# main.net
KiCad netlist of a schematic drawn in Altium Designer
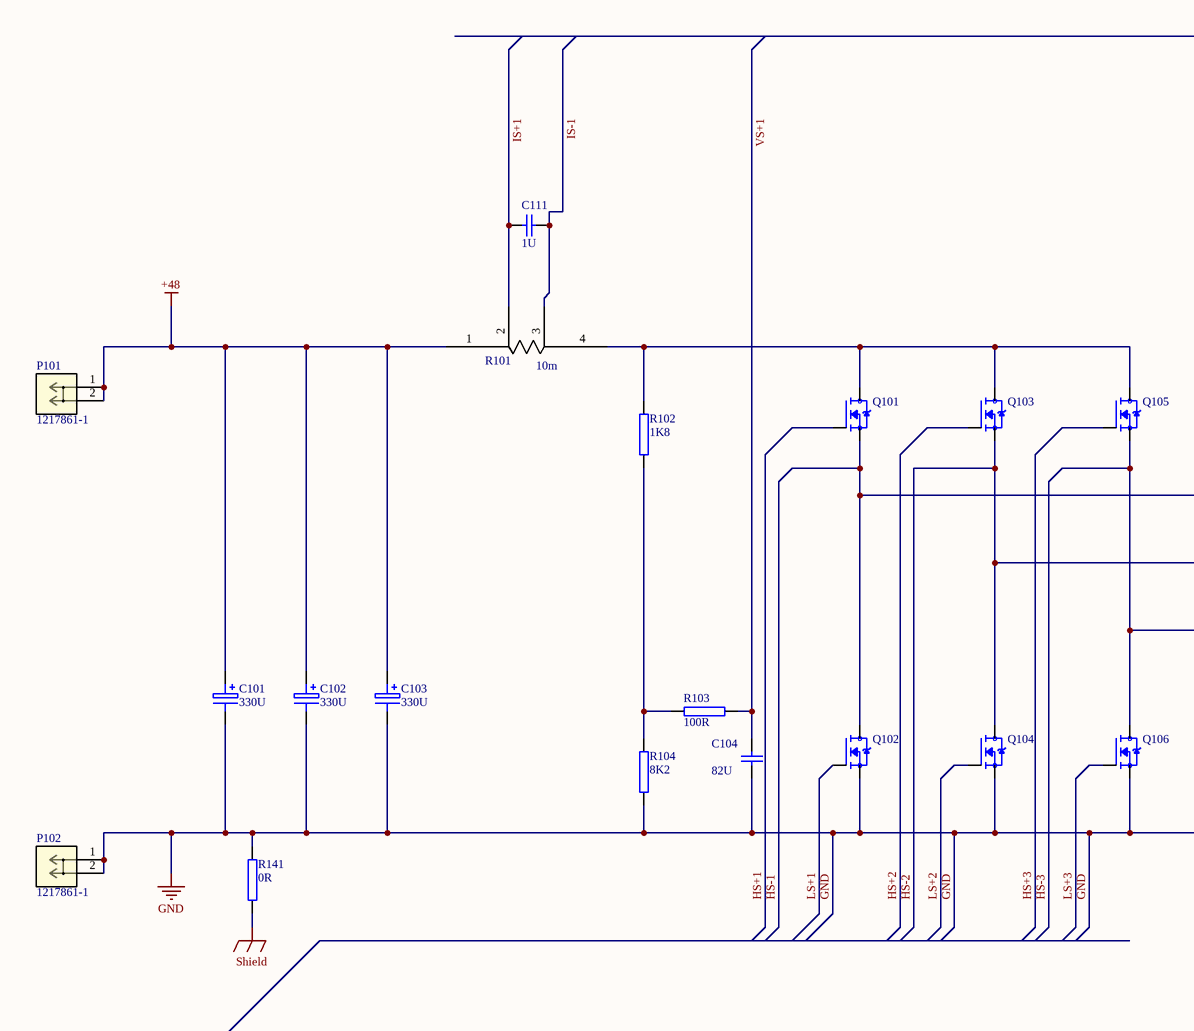
[diagram p0: main.SchDoc, top left]
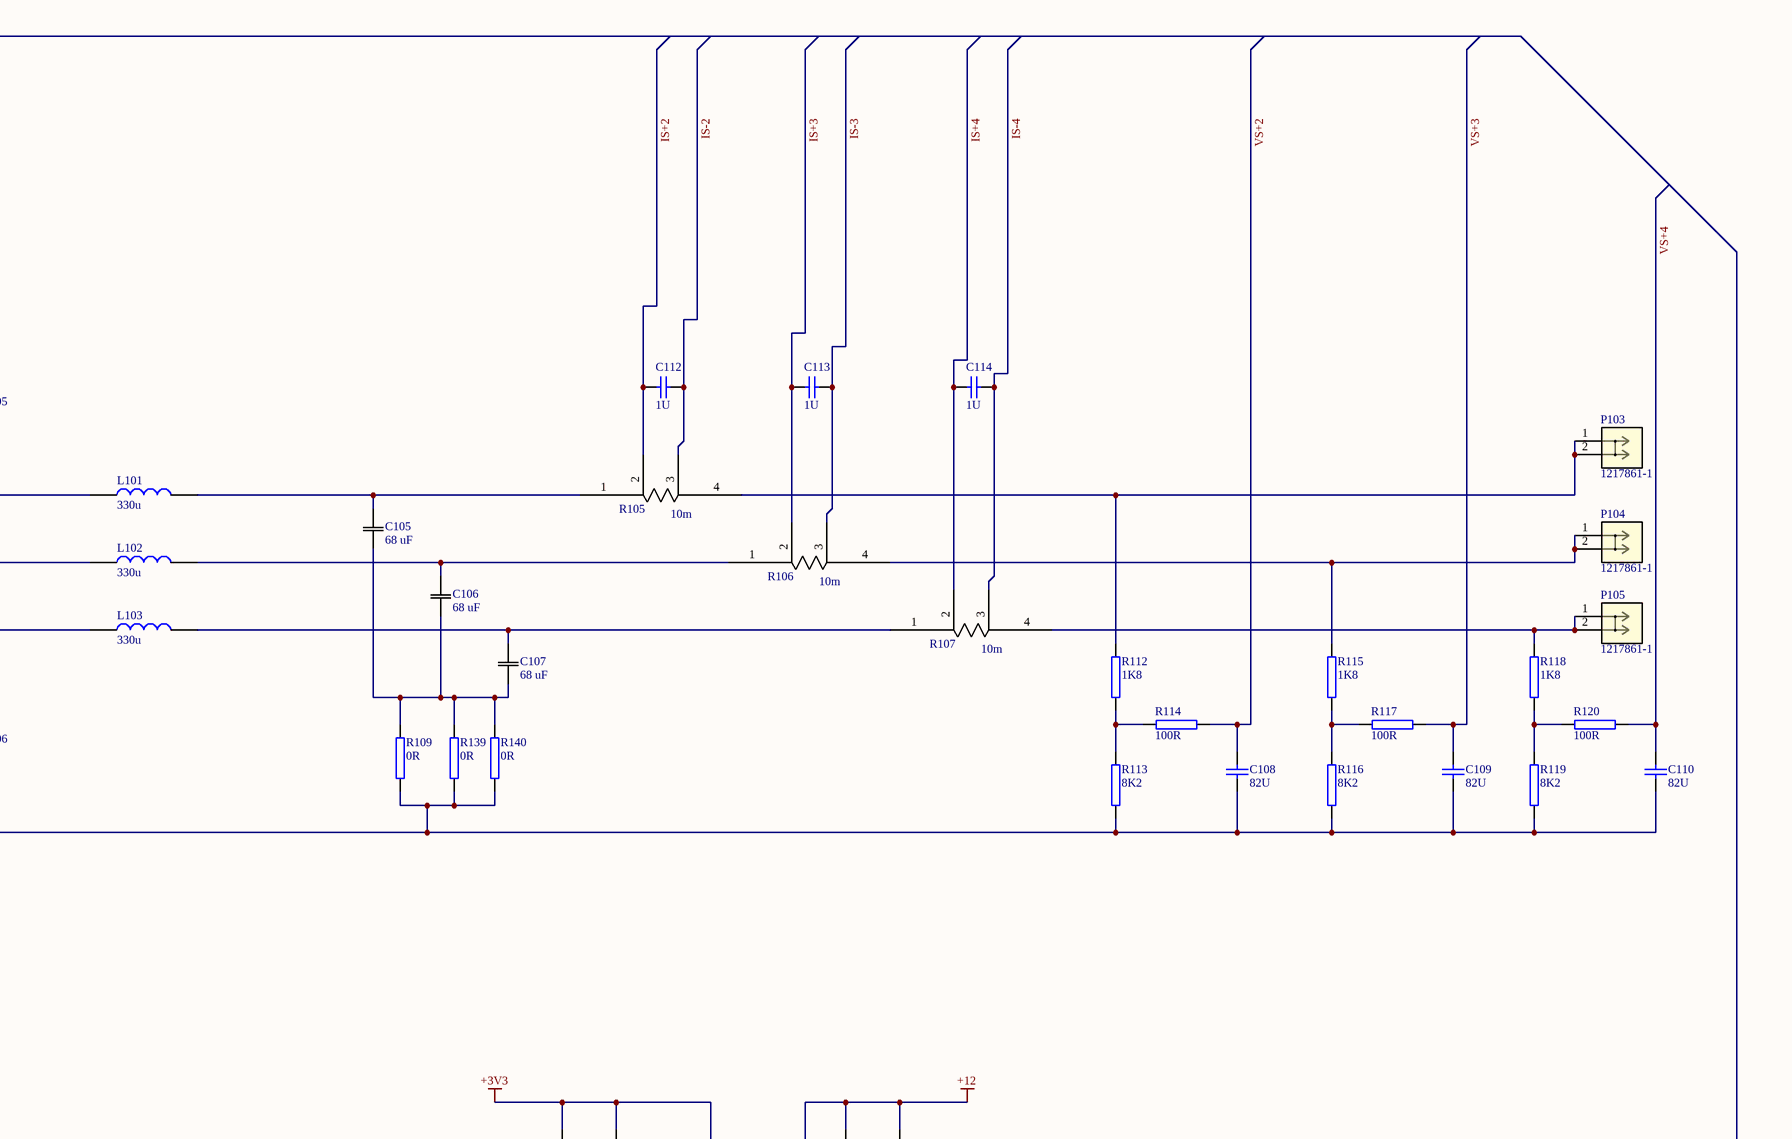
[diagram p1: main.SchDoc, top right]
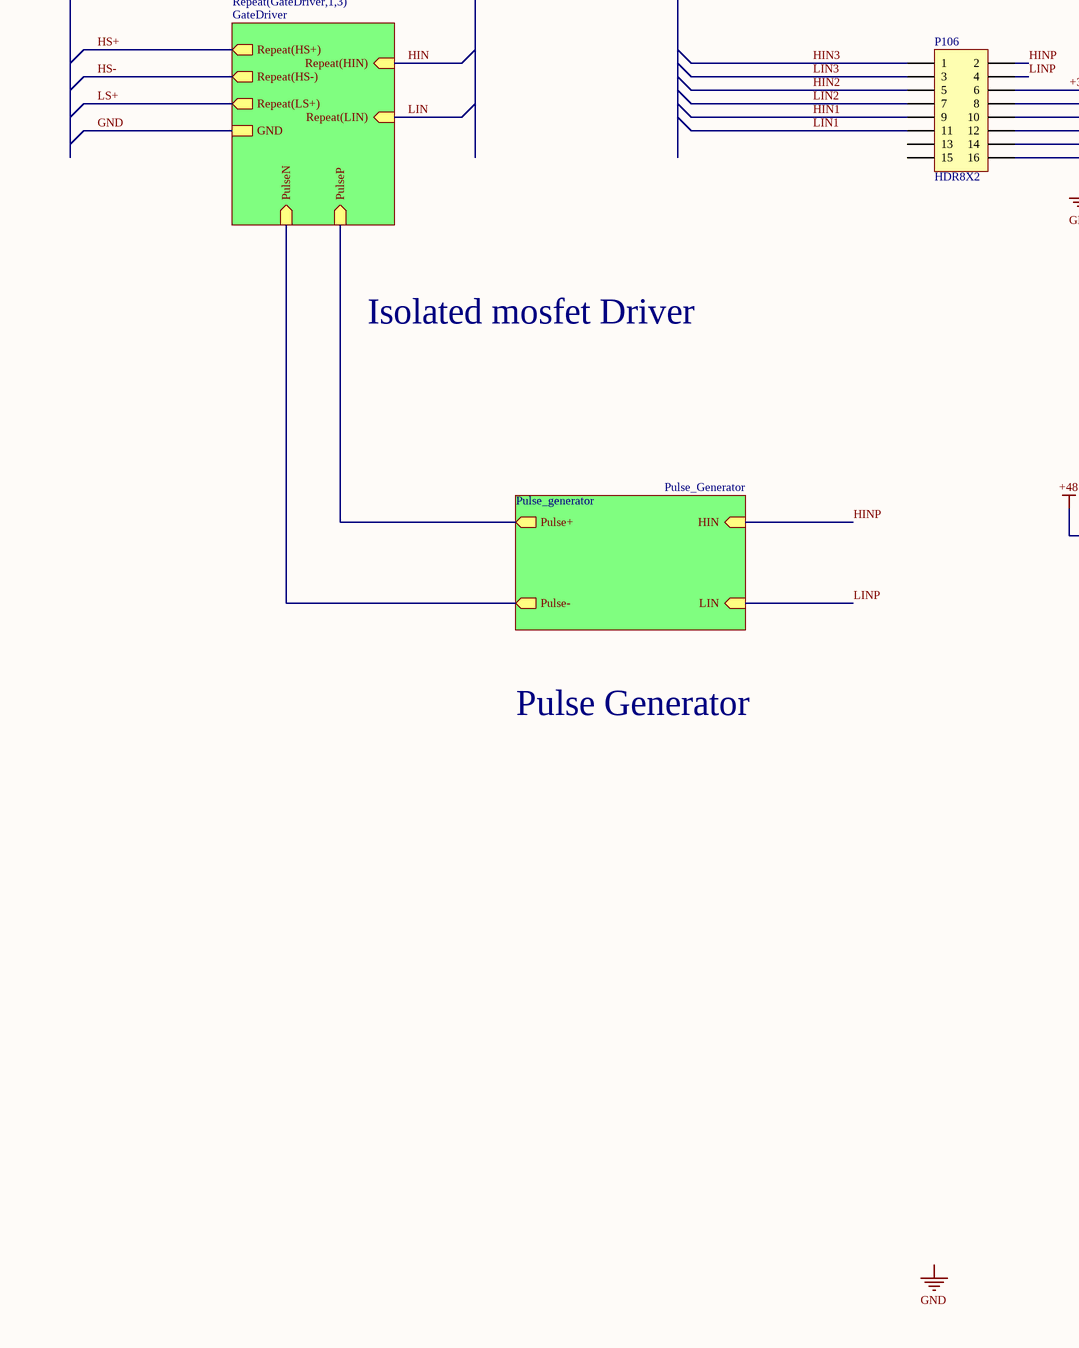
[diagram p2: main.SchDoc, bottom left]
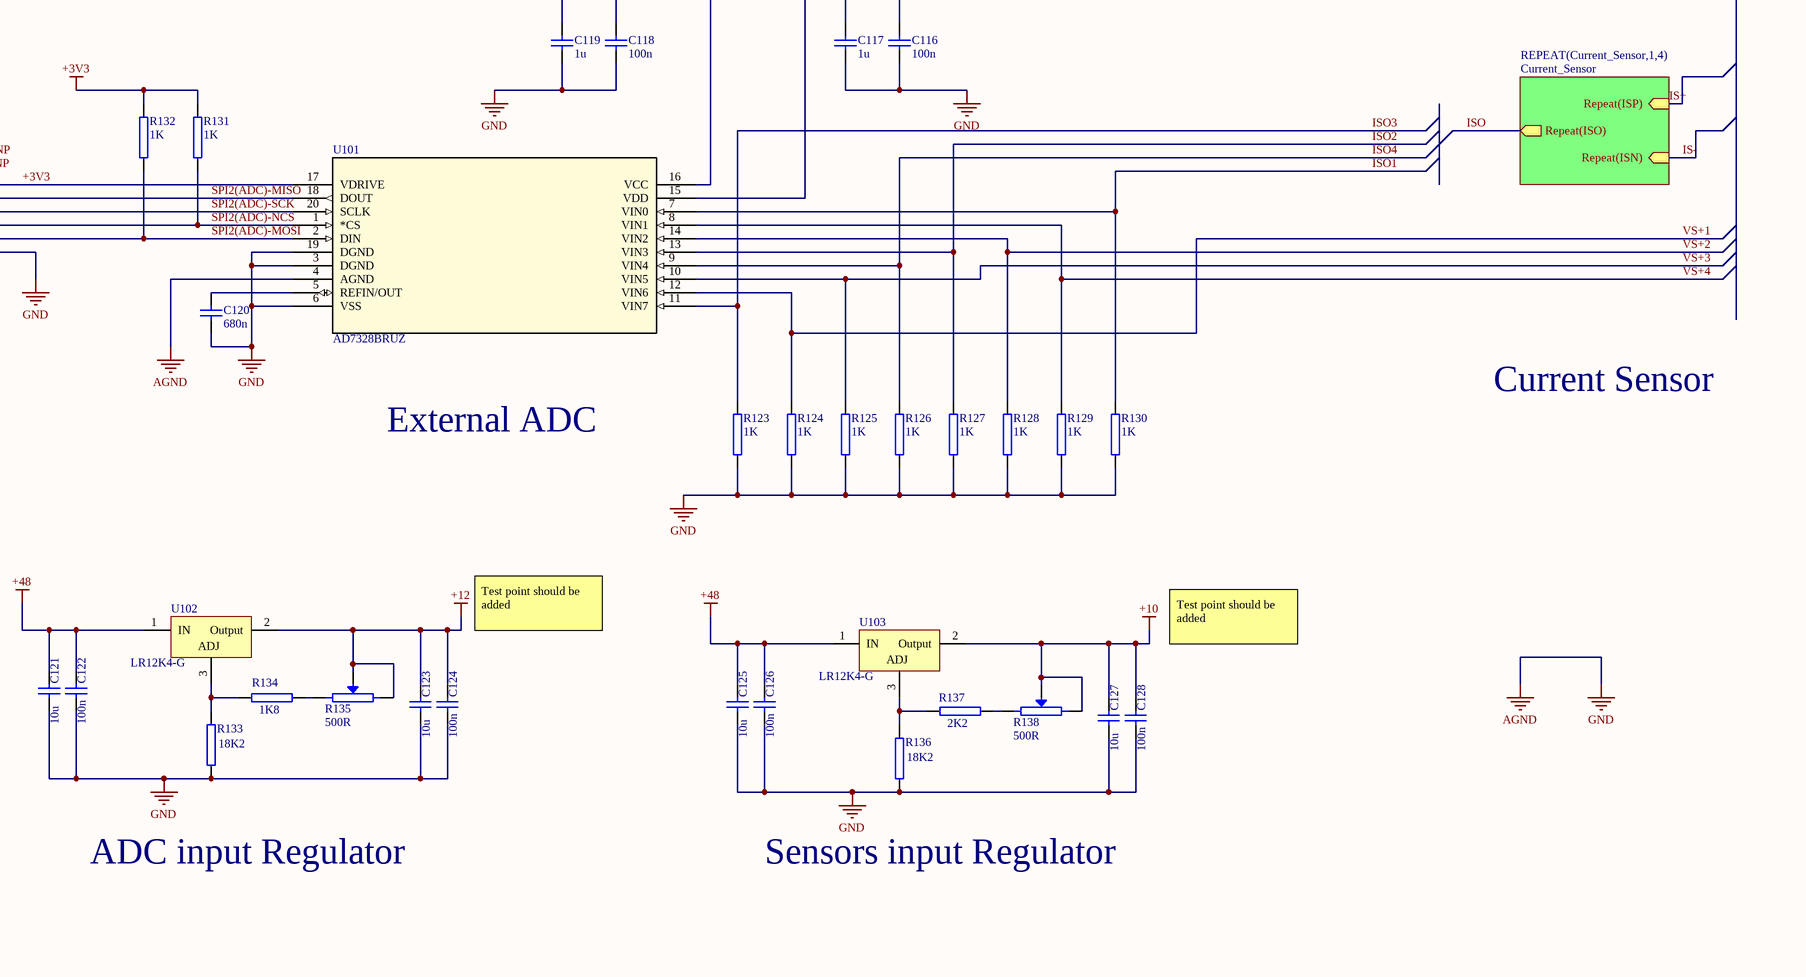
[diagram p3: main.SchDoc, bottom right]

(export (version "E")
  (design (tool "Eeschema 10.0.6"))
  (components
    (comp (ref "C101")
      (value "330U")
      (footprint "CAPP300-600_AUT")
      (description "Polarized Aluminum Capacitor, Through Hole, Pitch 300mil, Body 600mil (Dia)")
      (libsource (lib "Resistors and Capacitors") (part "CAPP300-600"))
    )
    (comp (ref "C102")
      (value "330U")
      (footprint "CAPP300-600_AUT")
      (description "Polarized Aluminum Capacitor, Through Hole, Pitch 300mil, Body 600mil (Dia)")
      (libsource (lib "Resistors and Capacitors") (part "CAPP300-600"))
    )
    (comp (ref "C103")
      (value "330U")
      (footprint "CAPP300-600_AUT")
      (description "Polarized Aluminum Capacitor, Through Hole, Pitch 300mil, Body 600mil (Dia)")
      (libsource (lib "Resistors and Capacitors") (part "CAPP300-600"))
    )
    (comp (ref "C104")
      (value "82U")
      (footprint "CAP_1206")
      (description "Non Polarized Capacitor, SMD, 1206")
      (libsource (lib "Resistors and Capacitors") (part "CAPN 1206"))
    )
    (comp (ref "C105")
      (value "68 uF")
      (footprint "B32526R3686K000")
      (libsource (lib "ENEL709_Schematic_Library") (part "B32526R3686K000"))
    )
    (comp (ref "C106")
      (value "68 uF")
      (footprint "B32526R3686K000")
      (libsource (lib "ENEL709_Schematic_Library") (part "B32526R3686K000"))
    )
    (comp (ref "C107")
      (value "68 uF")
      (footprint "B32526R3686K000")
      (libsource (lib "ENEL709_Schematic_Library") (part "B32526R3686K000"))
    )
    (comp (ref "C108")
      (value "82U")
      (footprint "CAP_1206")
      (description "Non Polarized Capacitor, SMD, 1206")
      (libsource (lib "Resistors and Capacitors") (part "CAPN 1206"))
    )
    (comp (ref "C109")
      (value "82U")
      (footprint "CAP_1206")
      (description "Non Polarized Capacitor, SMD, 1206")
      (libsource (lib "Resistors and Capacitors") (part "CAPN 1206"))
    )
    (comp (ref "C110")
      (value "82U")
      (footprint "CAP_1206")
      (description "Non Polarized Capacitor, SMD, 1206")
      (libsource (lib "Resistors and Capacitors") (part "CAPN 1206"))
    )
    (comp (ref "C111")
      (value "1U")
      (footprint "CAP_1206")
      (description "Non Polarized Capacitor, SMD, 1206")
      (libsource (lib "Resistors and Capacitors") (part "CAPN 1206"))
    )
    (comp (ref "C112")
      (value "1U")
      (footprint "CAP_1206")
      (description "Non Polarized Capacitor, SMD, 1206")
      (libsource (lib "Resistors and Capacitors") (part "CAPN 1206"))
    )
    (comp (ref "C113")
      (value "1U")
      (footprint "CAP_1206")
      (description "Non Polarized Capacitor, SMD, 1206")
      (libsource (lib "Resistors and Capacitors") (part "CAPN 1206"))
    )
    (comp (ref "C114")
      (value "1U")
      (footprint "CAP_1206")
      (description "Non Polarized Capacitor, SMD, 1206")
      (libsource (lib "Resistors and Capacitors") (part "CAPN 1206"))
    )
    (comp (ref "C116")
      (value "100n")
      (footprint "CAP_1206")
      (description "Non Polarized Capacitor, SMD, 1206")
      (libsource (lib "Resistors and Capacitors") (part "CAPN 1206"))
    )
    (comp (ref "C117")
      (value "1u")
      (footprint "CAP_1206")
      (description "Non Polarized Capacitor, SMD, 1206")
      (libsource (lib "Resistors and Capacitors") (part "CAPN 1206"))
    )
    (comp (ref "C118")
      (value "100n")
      (footprint "CAP_1206")
      (description "Non Polarized Capacitor, SMD, 1206")
      (libsource (lib "Resistors and Capacitors") (part "CAPN 1206"))
    )
    (comp (ref "C119")
      (value "1u")
      (footprint "CAP_1206")
      (description "Non Polarized Capacitor, SMD, 1206")
      (libsource (lib "Resistors and Capacitors") (part "CAPN 1206"))
    )
    (comp (ref "C120")
      (value "680n")
      (footprint "CAP_1206")
      (description "Non Polarized Capacitor, SMD, 1206")
      (libsource (lib "Resistors and Capacitors") (part "CAPN 1206"))
    )
    (comp (ref "C121")
      (value "10u")
      (footprint "CAP_1206")
      (description "Non Polarized Capacitor, SMD, 1206")
      (libsource (lib "Resistors and Capacitors") (part "CAPN 1206"))
    )
    (comp (ref "C122")
      (value "100n")
      (footprint "CAP_1206")
      (description "Non Polarized Capacitor, SMD, 1206")
      (libsource (lib "Resistors and Capacitors") (part "CAPN 1206"))
    )
    (comp (ref "C123")
      (value "10u")
      (footprint "CAP_1206")
      (description "Non Polarized Capacitor, SMD, 1206")
      (libsource (lib "Resistors and Capacitors") (part "CAPN 1206"))
    )
    (comp (ref "C124")
      (value "100n")
      (footprint "CAP_1206")
      (description "Non Polarized Capacitor, SMD, 1206")
      (libsource (lib "Resistors and Capacitors") (part "CAPN 1206"))
    )
    (comp (ref "C125")
      (value "10u")
      (footprint "CAP_1206")
      (description "Non Polarized Capacitor, SMD, 1206")
      (libsource (lib "Resistors and Capacitors") (part "CAPN 1206"))
    )
    (comp (ref "C126")
      (value "100n")
      (footprint "CAP_1206")
      (description "Non Polarized Capacitor, SMD, 1206")
      (libsource (lib "Resistors and Capacitors") (part "CAPN 1206"))
    )
    (comp (ref "C127")
      (value "10u")
      (footprint "CAP_1206")
      (description "Non Polarized Capacitor, SMD, 1206")
      (libsource (lib "Resistors and Capacitors") (part "CAPN 1206"))
    )
    (comp (ref "C128")
      (value "100n")
      (footprint "CAP_1206")
      (description "Non Polarized Capacitor, SMD, 1206")
      (libsource (lib "Resistors and Capacitors") (part "CAPN 1206"))
    )
    (comp (ref "L101")
      (value "330u")
      (footprint "1140-331K-RC")
      (libsource (lib "ENEL709_Schematic_Library") (part "1140-331K-RC"))
    )
    (comp (ref "L102")
      (value "330u")
      (footprint "1140-331K-RC")
      (libsource (lib "ENEL709_Schematic_Library") (part "1140-331K-RC"))
    )
    (comp (ref "L103")
      (value "330u")
      (footprint "1140-331K-RC")
      (libsource (lib "ENEL709_Schematic_Library") (part "1140-331K-RC"))
    )
    (comp (ref "P101")
      (value "1217861-1")
      (footprint "CONN_1217861-1_TEC")
      (libsource (lib "") (part "1217861-1_1"))
    )
    (comp (ref "P102")
      (value "1217861-1")
      (footprint "CONN_1217861-1_TEC")
      (libsource (lib "") (part "1217861-1_1"))
    )
    (comp (ref "P103")
      (value "1217861-1")
      (footprint "CONN_1217861-1_TEC")
      (libsource (lib "Schlib") (part "1217861-1"))
    )
    (comp (ref "P104")
      (value "1217861-1")
      (footprint "CONN_1217861-1_TEC")
      (libsource (lib "Schlib") (part "1217861-1"))
    )
    (comp (ref "P105")
      (value "1217861-1")
      (footprint "CONN_1217861-1_TEC")
      (libsource (lib "Schlib") (part "1217861-1"))
    )
    (comp (ref "P106")
      (value "HDR8X2")
      (footprint "HDR2X8_AUT")
      (description "Header, 8-Pin, Dual row, 2.54mm Pitch, Straight")
      (libsource (lib "Connectors") (part "HDR8X2"))
    )
    (comp (ref "Q101")
      (value "MCTL80N20Y-TP")
      (footprint "TOLL-8L")
      (description "N-Channel 200 V 80A (Tc) 250W (Tj) Surface Mount TOLL-8L")
      (libsource (lib "Projects_2025") (part "MCTL80N20Y-TP"))
    )
    (comp (ref "Q102")
      (value "MCTL80N20Y-TP")
      (footprint "TOLL-8L")
      (description "N-Channel 200 V 80A (Tc) 250W (Tj) Surface Mount TOLL-8L")
      (libsource (lib "Projects_2025") (part "MCTL80N20Y-TP"))
    )
    (comp (ref "Q103")
      (value "MCTL80N20Y-TP")
      (footprint "TOLL-8L")
      (description "N-Channel 200 V 80A (Tc) 250W (Tj) Surface Mount TOLL-8L")
      (libsource (lib "Projects_2025") (part "MCTL80N20Y-TP"))
    )
    (comp (ref "Q104")
      (value "MCTL80N20Y-TP")
      (footprint "TOLL-8L")
      (description "N-Channel 200 V 80A (Tc) 250W (Tj) Surface Mount TOLL-8L")
      (libsource (lib "Projects_2025") (part "MCTL80N20Y-TP"))
    )
    (comp (ref "Q105")
      (value "MCTL80N20Y-TP")
      (footprint "TOLL-8L")
      (description "N-Channel 200 V 80A (Tc) 250W (Tj) Surface Mount TOLL-8L")
      (libsource (lib "Projects_2025") (part "MCTL80N20Y-TP"))
    )
    (comp (ref "Q106")
      (value "MCTL80N20Y-TP")
      (footprint "TOLL-8L")
      (description "N-Channel 200 V 80A (Tc) 250W (Tj) Surface Mount TOLL-8L")
      (libsource (lib "Projects_2025") (part "MCTL80N20Y-TP"))
    )
    (comp (ref "R101")
      (value "10m")
      (footprint "WSL3673R_002-01")
      (description "Current Shunt \r\nKelvin 4W 0.002- 0.01")
      (libsource (lib "Projects_2025") (part "WSL3673R-01"))
    )
    (comp (ref "R102")
      (value "1K8")
      (footprint "RES_1206")
      (description "Resistor, SMD, 1206")
      (libsource (lib "Resistors and Capacitors") (part "Resistor 1206"))
    )
    (comp (ref "R103")
      (value "100R")
      (footprint "RES_1206")
      (description "Resistor, SMD, 1206")
      (libsource (lib "Resistors and Capacitors") (part "Resistor 1206"))
    )
    (comp (ref "R104")
      (value "8K2")
      (footprint "RES_1206")
      (description "Resistor, SMD, 1206")
      (libsource (lib "Resistors and Capacitors") (part "Resistor 1206"))
    )
    (comp (ref "R105")
      (value "10m")
      (footprint "WSL3673R_002-01")
      (description "Current Shunt \r\nKelvin 4W 0.002- 0.01")
      (libsource (lib "Projects_2025") (part "WSL3673R-01"))
    )
    (comp (ref "R106")
      (value "10m")
      (footprint "WSL3673R_002-01")
      (description "Current Shunt \r\nKelvin 4W 0.002- 0.01")
      (libsource (lib "Projects_2025") (part "WSL3673R-01"))
    )
    (comp (ref "R107")
      (value "10m")
      (footprint "WSL3673R_002-01")
      (description "Current Shunt \r\nKelvin 4W 0.002- 0.01")
      (libsource (lib "Projects_2025") (part "WSL3673R-01"))
    )
    (comp (ref "R109")
      (value "0R")
      (footprint "RES_1206")
      (description "Resistor, SMD, 1206")
      (libsource (lib "Resistors and Capacitors") (part "Resistor 1206"))
    )
    (comp (ref "R112")
      (value "1K8")
      (footprint "RES_1206")
      (description "Resistor, SMD, 1206")
      (libsource (lib "Resistors and Capacitors") (part "Resistor 1206"))
    )
    (comp (ref "R113")
      (value "8K2")
      (footprint "RES_1206")
      (description "Resistor, SMD, 1206")
      (libsource (lib "Resistors and Capacitors") (part "Resistor 1206"))
    )
    (comp (ref "R114")
      (value "100R")
      (footprint "RES_1206")
      (description "Resistor, SMD, 1206")
      (libsource (lib "Resistors and Capacitors") (part "Resistor 1206"))
    )
    (comp (ref "R115")
      (value "1K8")
      (footprint "RES_1206")
      (description "Resistor, SMD, 1206")
      (libsource (lib "Resistors and Capacitors") (part "Resistor 1206"))
    )
    (comp (ref "R116")
      (value "8K2")
      (footprint "RES_1206")
      (description "Resistor, SMD, 1206")
      (libsource (lib "Resistors and Capacitors") (part "Resistor 1206"))
    )
    (comp (ref "R117")
      (value "100R")
      (footprint "RES_1206")
      (description "Resistor, SMD, 1206")
      (libsource (lib "Resistors and Capacitors") (part "Resistor 1206"))
    )
    (comp (ref "R118")
      (value "1K8")
      (footprint "RES_1206")
      (description "Resistor, SMD, 1206")
      (libsource (lib "Resistors and Capacitors") (part "Resistor 1206"))
    )
    (comp (ref "R119")
      (value "8K2")
      (footprint "RES_1206")
      (description "Resistor, SMD, 1206")
      (libsource (lib "Resistors and Capacitors") (part "Resistor 1206"))
    )
    (comp (ref "R120")
      (value "100R")
      (footprint "RES_1206")
      (description "Resistor, SMD, 1206")
      (libsource (lib "Resistors and Capacitors") (part "Resistor 1206"))
    )
    (comp (ref "R123")
      (value "1K")
      (footprint "RES_1206")
      (description "Resistor, SMD, 1206")
      (libsource (lib "Resistors and Capacitors") (part "Resistor 1206"))
    )
    (comp (ref "R124")
      (value "1K")
      (footprint "RES_1206")
      (description "Resistor, SMD, 1206")
      (libsource (lib "Resistors and Capacitors") (part "Resistor 1206"))
    )
    (comp (ref "R125")
      (value "1K")
      (footprint "RES_1206")
      (description "Resistor, SMD, 1206")
      (libsource (lib "Resistors and Capacitors") (part "Resistor 1206"))
    )
    (comp (ref "R126")
      (value "1K")
      (footprint "RES_1206")
      (description "Resistor, SMD, 1206")
      (libsource (lib "Resistors and Capacitors") (part "Resistor 1206"))
    )
    (comp (ref "R127")
      (value "1K")
      (footprint "RES_1206")
      (description "Resistor, SMD, 1206")
      (libsource (lib "Resistors and Capacitors") (part "Resistor 1206"))
    )
    (comp (ref "R128")
      (value "1K")
      (footprint "RES_1206")
      (description "Resistor, SMD, 1206")
      (libsource (lib "Resistors and Capacitors") (part "Resistor 1206"))
    )
    (comp (ref "R129")
      (value "1K")
      (footprint "RES_1206")
      (description "Resistor, SMD, 1206")
      (libsource (lib "Resistors and Capacitors") (part "Resistor 1206"))
    )
    (comp (ref "R130")
      (value "1K")
      (footprint "RES_1206")
      (description "Resistor, SMD, 1206")
      (libsource (lib "Resistors and Capacitors") (part "Resistor 1206"))
    )
    (comp (ref "R131")
      (value "1K")
      (footprint "RES_1206")
      (description "Resistor, SMD, 1206")
      (libsource (lib "Resistors and Capacitors") (part "Resistor 1206"))
    )
    (comp (ref "R132")
      (value "1K")
      (footprint "RES_1206")
      (description "Resistor, SMD, 1206")
      (libsource (lib "Resistors and Capacitors") (part "Resistor 1206"))
    )
    (comp (ref "R133")
      (value "18K2")
      (footprint "RES_1206")
      (description "Resistor, SMD, 1206")
      (libsource (lib "Resistors and Capacitors") (part "Resistor 1206"))
    )
    (comp (ref "R134")
      (value "1K8")
      (footprint "RES_1206")
      (description "Resistor, SMD, 1206")
      (libsource (lib "Resistors and Capacitors") (part "Resistor 1206"))
    )
    (comp (ref "R135")
      (value "500R")
      (footprint "3296W")
      (libsource (lib "Potentiometers") (part "3296W-1-104LF"))
    )
    (comp (ref "R136")
      (value "18K2")
      (footprint "RES_1206")
      (description "Resistor, SMD, 1206")
      (libsource (lib "Resistors and Capacitors") (part "Resistor 1206"))
    )
    (comp (ref "R137")
      (value "2K2")
      (footprint "RES_1206")
      (description "Resistor, SMD, 1206")
      (libsource (lib "Resistors and Capacitors") (part "Resistor 1206"))
    )
    (comp (ref "R138")
      (value "500R")
      (footprint "3296W")
      (libsource (lib "Potentiometers") (part "3296W-1-104LF"))
    )
    (comp (ref "R139")
      (value "0R")
      (footprint "RES_1206")
      (description "Resistor, SMD, 1206")
      (libsource (lib "Resistors and Capacitors") (part "Resistor 1206"))
    )
    (comp (ref "R140")
      (value "0R")
      (footprint "RES_1206")
      (description "Resistor, SMD, 1206")
      (libsource (lib "Resistors and Capacitors") (part "Resistor 1206"))
    )
    (comp (ref "R141")
      (value "0R")
      (footprint "RES_1206")
      (description "Resistor, SMD, 1206")
      (libsource (lib "Resistors and Capacitors") (part "Resistor 1206"))
    )
    (comp (ref "U101")
      (value "AD7328BRUZ")
      (footprint "TSSOP20_44")
      (description "ADC 12 Bit\r\nPackage TSSOP20")
      (libsource (lib "Projects_2025") (part "AD7328BRUZ"))
    )
    (comp (ref "U102")
      (value "LR12K4-G")
      (footprint "D PAK (TO-252-3)")
      (description "Adj Positive Regulator \r\nLinear. 12V dropout V. \r\n2W")
      (libsource (lib "Projects_2025") (part "LR12K4-G"))
    )
    (comp (ref "U103")
      (value "LR12K4-G")
      (footprint "D PAK (TO-252-3)")
      (description "Adj Positive Regulator \r\nLinear. 12V dropout V. \r\n2W")
      (libsource (lib "Projects_2025") (part "LR12K4-G"))
    )
  )
  (nets
    (net (code "1") (name "+3V3") (class "Default")
      (node (ref "C118") (pin "2") (pinfunction "2_2") (pintype "passive"))
      (node (ref "C119") (pin "2") (pinfunction "2_2") (pintype "passive"))
      (node (ref "P106") (pin "6") (pinfunction "6_6") (pintype "passive"))
      (node (ref "R131") (pin "2") (pinfunction "2_2") (pintype "passive"))
      (node (ref "R132") (pin "2") (pinfunction "2_2") (pintype "passive"))
      (node (ref "U101") (pin "16") (pinfunction "VCC_16") (pintype "power_in"))
      (node (ref "U101") (pin "17") (pinfunction "VDRIVE_17") (pintype "power_in"))
    )
    (net (code "2") (name "+10") (class "Default")
      (node (ref "C127") (pin "2") (pinfunction "2_2") (pintype "passive"))
      (node (ref "C128") (pin "2") (pinfunction "2_2") (pintype "passive"))
      (node (ref "R138") (pin "2") (pinfunction "BOT_2") (pintype "passive"))
      (node (ref "R138") (pin "W") (pinfunction "TAP_W") (pintype "passive"))
      (node (ref "U103") (pin "2") (pinfunction "Output_2") (pintype "power_in"))
    )
    (net (code "3") (name "+12") (class "Default")
      (node (ref "C116") (pin "2") (pinfunction "2_2") (pintype "passive"))
      (node (ref "C117") (pin "2") (pinfunction "2_2") (pintype "passive"))
      (node (ref "C123") (pin "2") (pinfunction "2_2") (pintype "passive"))
      (node (ref "C124") (pin "2") (pinfunction "2_2") (pintype "passive"))
      (node (ref "R135") (pin "2") (pinfunction "BOT_2") (pintype "passive"))
      (node (ref "R135") (pin "W") (pinfunction "TAP_W") (pintype "passive"))
      (node (ref "U101") (pin "15") (pinfunction "VDD_15") (pintype "power_in"))
      (node (ref "U102") (pin "2") (pinfunction "Output_2") (pintype "power_in"))
    )
    (net (code "4") (name "+48") (class "Default")
      (node (ref "C101") (pin "1") (pinfunction "1_1") (pintype "passive"))
      (node (ref "C102") (pin "1") (pinfunction "1_1") (pintype "passive"))
      (node (ref "C103") (pin "1") (pinfunction "1_1") (pintype "passive"))
      (node (ref "C121") (pin "2") (pinfunction "2_2") (pintype "passive"))
      (node (ref "C122") (pin "2") (pinfunction "2_2") (pintype "passive"))
      (node (ref "C125") (pin "2") (pinfunction "2_2") (pintype "passive"))
      (node (ref "C126") (pin "2") (pinfunction "2_2") (pintype "passive"))
      (node (ref "P101") (pin "1") (pinfunction "1_1") (pintype "passive"))
      (node (ref "P101") (pin "2") (pinfunction "2_2") (pintype "passive"))
      (node (ref "R101") (pin "1") (pinfunction "1_1") (pintype "passive"))
      (node (ref "U102") (pin "1") (pinfunction "IN_1") (pintype "power_in"))
      (node (ref "U103") (pin "1") (pinfunction "IN_1") (pintype "power_in"))
    )
    (net (code "6") (name "/HIN1") (class "Default")
      (node (ref "P106") (pin "9") (pinfunction "9_9") (pintype "passive"))
    )
    (net (code "7") (name "/HIN2") (class "Default")
      (node (ref "P106") (pin "5") (pinfunction "5_5") (pintype "passive"))
    )
    (net (code "8") (name "/HIN3") (class "Default")
      (node (ref "P106") (pin "1") (pinfunction "1_1") (pintype "passive"))
    )
    (net (code "9") (name "/HINP") (class "Default")
      (node (ref "P106") (pin "2") (pinfunction "2_2") (pintype "passive"))
    )
    (net (code "11") (name "/HS+1") (class "Default")
      (node (ref "Q101") (pin "1") (pinfunction "G_1") (pintype "passive"))
    )
    (net (code "12") (name "/HS+2") (class "Default")
      (node (ref "Q103") (pin "1") (pinfunction "G_1") (pintype "passive"))
    )
    (net (code "13") (name "/HS+3") (class "Default")
      (node (ref "Q105") (pin "1") (pinfunction "G_1") (pintype "passive"))
    )
    (net (code "15") (name "/HS-1") (class "Default")
      (node (ref "L101") (pin "1") (pinfunction "1_1") (pintype "passive"))
      (node (ref "Q101") (pin "2") (pinfunction "S_2") (pintype "passive"))
      (node (ref "Q102") (pin "3") (pinfunction "D_3") (pintype "passive"))
    )
    (net (code "16") (name "/HS-2") (class "Default")
      (node (ref "L102") (pin "1") (pinfunction "1_1") (pintype "passive"))
      (node (ref "Q103") (pin "2") (pinfunction "S_2") (pintype "passive"))
      (node (ref "Q104") (pin "3") (pinfunction "D_3") (pintype "passive"))
    )
    (net (code "17") (name "/HS-3") (class "Default")
      (node (ref "L103") (pin "1") (pinfunction "1_1") (pintype "passive"))
      (node (ref "Q105") (pin "2") (pinfunction "S_2") (pintype "passive"))
      (node (ref "Q106") (pin "3") (pinfunction "D_3") (pintype "passive"))
    )
    (net (code "19") (name "/IS+1") (class "Default")
      (node (ref "C111") (pin "2") (pinfunction "2_2") (pintype "passive"))
      (node (ref "R101") (pin "2") (pinfunction "2_2") (pintype "passive"))
    )
    (net (code "20") (name "/IS+2") (class "Default")
      (node (ref "C112") (pin "2") (pinfunction "2_2") (pintype "passive"))
      (node (ref "R105") (pin "2") (pinfunction "2_2") (pintype "passive"))
    )
    (net (code "21") (name "/IS+3") (class "Default")
      (node (ref "C113") (pin "2") (pinfunction "2_2") (pintype "passive"))
      (node (ref "R106") (pin "2") (pinfunction "2_2") (pintype "passive"))
    )
    (net (code "22") (name "/IS+4") (class "Default")
      (node (ref "C114") (pin "2") (pinfunction "2_2") (pintype "passive"))
      (node (ref "R107") (pin "2") (pinfunction "2_2") (pintype "passive"))
    )
    (net (code "24") (name "/IS-1") (class "Default")
      (node (ref "C111") (pin "1") (pinfunction "1_1") (pintype "passive"))
      (node (ref "R101") (pin "3") (pinfunction "3_3") (pintype "passive"))
    )
    (net (code "25") (name "/IS-2") (class "Default")
      (node (ref "C112") (pin "1") (pinfunction "1_1") (pintype "passive"))
      (node (ref "R105") (pin "3") (pinfunction "3_3") (pintype "passive"))
    )
    (net (code "26") (name "/IS-3") (class "Default")
      (node (ref "C113") (pin "1") (pinfunction "1_1") (pintype "passive"))
      (node (ref "R106") (pin "3") (pinfunction "3_3") (pintype "passive"))
    )
    (net (code "27") (name "/IS-4") (class "Default")
      (node (ref "C114") (pin "1") (pinfunction "1_1") (pintype "passive"))
      (node (ref "R107") (pin "3") (pinfunction "3_3") (pintype "passive"))
    )
    (net (code "29") (name "/ISO1") (class "Default")
      (node (ref "R130") (pin "2") (pinfunction "2_2") (pintype "passive"))
      (node (ref "U101") (pin "7") (pinfunction "VIN0_7") (pintype "input"))
    )
    (net (code "30") (name "/ISO2") (class "Default")
      (node (ref "R127") (pin "2") (pinfunction "2_2") (pintype "passive"))
      (node (ref "U101") (pin "13") (pinfunction "VIN3_13") (pintype "input"))
    )
    (net (code "31") (name "/ISO3") (class "Default")
      (node (ref "R123") (pin "2") (pinfunction "2_2") (pintype "passive"))
      (node (ref "U101") (pin "11") (pinfunction "VIN7_11") (pintype "input"))
    )
    (net (code "32") (name "/ISO4") (class "Default")
      (node (ref "R126") (pin "2") (pinfunction "2_2") (pintype "passive"))
      (node (ref "U101") (pin "9") (pinfunction "VIN4_9") (pintype "input"))
    )
    (net (code "34") (name "/LIN1") (class "Default")
      (node (ref "P106") (pin "11") (pinfunction "11_11") (pintype "passive"))
    )
    (net (code "35") (name "/LIN2") (class "Default")
      (node (ref "P106") (pin "7") (pinfunction "7_7") (pintype "passive"))
    )
    (net (code "36") (name "/LIN3") (class "Default")
      (node (ref "P106") (pin "3") (pinfunction "3_3") (pintype "passive"))
    )
    (net (code "37") (name "/LINP") (class "Default")
      (node (ref "P106") (pin "4") (pinfunction "4_4") (pintype "passive"))
    )
    (net (code "39") (name "/LS+1") (class "Default")
      (node (ref "Q102") (pin "1") (pinfunction "G_1") (pintype "passive"))
    )
    (net (code "40") (name "/LS+2") (class "Default")
      (node (ref "Q104") (pin "1") (pinfunction "G_1") (pintype "passive"))
    )
    (net (code "41") (name "/LS+3") (class "Default")
      (node (ref "Q106") (pin "1") (pinfunction "G_1") (pintype "passive"))
    )
    (net (code "44") (name "/SPI2(ADC)-MISO") (class "Default")
      (node (ref "P106") (pin "8") (pinfunction "8_8") (pintype "passive"))
      (node (ref "U101") (pin "18") (pinfunction "DOUT_18") (pintype "output"))
    )
    (net (code "45") (name "/SPI2(ADC)-MOSI") (class "Default")
      (node (ref "P106") (pin "14") (pinfunction "14_14") (pintype "passive"))
      (node (ref "R132") (pin "1") (pinfunction "1_1") (pintype "passive"))
      (node (ref "U101") (pin "2") (pinfunction "DIN_2") (pintype "input"))
    )
    (net (code "46") (name "/SPI2(ADC)-NCS") (class "Default")
      (node (ref "P106") (pin "12") (pinfunction "12_12") (pintype "passive"))
      (node (ref "R131") (pin "1") (pinfunction "1_1") (pintype "passive"))
      (node (ref "U101") (pin "1") (pinfunction "*CS_1") (pintype "input"))
    )
    (net (code "47") (name "/SPI2(ADC)-SCK") (class "Default")
      (node (ref "P106") (pin "10") (pinfunction "10_10") (pintype "passive"))
      (node (ref "U101") (pin "20") (pinfunction "SCLK_20") (pintype "input"))
    )
    (net (code "48") (name "/VS+1") (class "Default")
      (node (ref "C104") (pin "2") (pinfunction "2_2") (pintype "passive"))
      (node (ref "R103") (pin "1") (pinfunction "1_1") (pintype "passive"))
      (node (ref "R124") (pin "2") (pinfunction "2_2") (pintype "passive"))
      (node (ref "U101") (pin "12") (pinfunction "VIN6_12") (pintype "input"))
    )
    (net (code "49") (name "/VS+2") (class "Default")
      (node (ref "C108") (pin "2") (pinfunction "2_2") (pintype "passive"))
      (node (ref "R114") (pin "1") (pinfunction "1_1") (pintype "passive"))
      (node (ref "R128") (pin "2") (pinfunction "2_2") (pintype "passive"))
      (node (ref "U101") (pin "14") (pinfunction "VIN2_14") (pintype "input"))
    )
    (net (code "50") (name "/VS+3") (class "Default")
      (node (ref "C109") (pin "2") (pinfunction "2_2") (pintype "passive"))
      (node (ref "R117") (pin "1") (pinfunction "1_1") (pintype "passive"))
      (node (ref "R125") (pin "2") (pinfunction "2_2") (pintype "passive"))
      (node (ref "U101") (pin "10") (pinfunction "VIN5_10") (pintype "input"))
    )
    (net (code "51") (name "/VS+4") (class "Default")
      (node (ref "C110") (pin "2") (pinfunction "2_2") (pintype "passive"))
      (node (ref "R120") (pin "1") (pinfunction "1_1") (pintype "passive"))
      (node (ref "R129") (pin "2") (pinfunction "2_2") (pintype "passive"))
      (node (ref "U101") (pin "8") (pinfunction "VIN1_8") (pintype "input"))
    )
    (net (code "52") (name "AGND") (class "Default")
      (node (ref "C101") (pin "2") (pinfunction "2_2") (pintype "passive"))
      (node (ref "C102") (pin "2") (pinfunction "2_2") (pintype "passive"))
      (node (ref "C103") (pin "2") (pinfunction "2_2") (pintype "passive"))
      (node (ref "C104") (pin "1") (pinfunction "1_1") (pintype "passive"))
      (node (ref "C108") (pin "1") (pinfunction "1_1") (pintype "passive"))
      (node (ref "C109") (pin "1") (pinfunction "1_1") (pintype "passive"))
      (node (ref "C110") (pin "1") (pinfunction "1_1") (pintype "passive"))
      (node (ref "C116") (pin "1") (pinfunction "1_1") (pintype "passive"))
      (node (ref "C117") (pin "1") (pinfunction "1_1") (pintype "passive"))
      (node (ref "C118") (pin "1") (pinfunction "1_1") (pintype "passive"))
      (node (ref "C119") (pin "1") (pinfunction "1_1") (pintype "passive"))
      (node (ref "C120") (pin "1") (pinfunction "1_1") (pintype "passive"))
      (node (ref "C121") (pin "1") (pinfunction "1_1") (pintype "passive"))
      (node (ref "C122") (pin "1") (pinfunction "1_1") (pintype "passive"))
      (node (ref "C123") (pin "1") (pinfunction "1_1") (pintype "passive"))
      (node (ref "C124") (pin "1") (pinfunction "1_1") (pintype "passive"))
      (node (ref "C125") (pin "1") (pinfunction "1_1") (pintype "passive"))
      (node (ref "C126") (pin "1") (pinfunction "1_1") (pintype "passive"))
      (node (ref "C127") (pin "1") (pinfunction "1_1") (pintype "passive"))
      (node (ref "C128") (pin "1") (pinfunction "1_1") (pintype "passive"))
      (node (ref "P102") (pin "1") (pinfunction "1_1") (pintype "passive"))
      (node (ref "P102") (pin "2") (pinfunction "2_2") (pintype "passive"))
      (node (ref "P106") (pin "16") (pinfunction "16_16") (pintype "passive"))
      (node (ref "Q102") (pin "2") (pinfunction "S_2") (pintype "passive"))
      (node (ref "Q104") (pin "2") (pinfunction "S_2") (pintype "passive"))
      (node (ref "Q106") (pin "2") (pinfunction "S_2") (pintype "passive"))
      (node (ref "R104") (pin "1") (pinfunction "1_1") (pintype "passive"))
      (node (ref "R109") (pin "2") (pinfunction "2_2") (pintype "passive"))
      (node (ref "R113") (pin "1") (pinfunction "1_1") (pintype "passive"))
      (node (ref "R116") (pin "1") (pinfunction "1_1") (pintype "passive"))
      (node (ref "R119") (pin "1") (pinfunction "1_1") (pintype "passive"))
      (node (ref "R123") (pin "1") (pinfunction "1_1") (pintype "passive"))
      (node (ref "R124") (pin "1") (pinfunction "1_1") (pintype "passive"))
      (node (ref "R125") (pin "1") (pinfunction "1_1") (pintype "passive"))
      (node (ref "R126") (pin "1") (pinfunction "1_1") (pintype "passive"))
      (node (ref "R127") (pin "1") (pinfunction "1_1") (pintype "passive"))
      (node (ref "R128") (pin "1") (pinfunction "1_1") (pintype "passive"))
      (node (ref "R129") (pin "1") (pinfunction "1_1") (pintype "passive"))
      (node (ref "R130") (pin "1") (pinfunction "1_1") (pintype "passive"))
      (node (ref "R133") (pin "1") (pinfunction "1_1") (pintype "passive"))
      (node (ref "R136") (pin "1") (pinfunction "1_1") (pintype "passive"))
      (node (ref "R139") (pin "2") (pinfunction "2_2") (pintype "passive"))
      (node (ref "R140") (pin "2") (pinfunction "2_2") (pintype "passive"))
      (node (ref "R141") (pin "2") (pinfunction "2_2") (pintype "passive"))
      (node (ref "U101") (pin "19") (pinfunction "DGND_19") (pintype "power_in"))
      (node (ref "U101") (pin "3") (pinfunction "DGND_3") (pintype "power_in"))
      (node (ref "U101") (pin "4") (pinfunction "AGND_4") (pintype "power_in"))
      (node (ref "U101") (pin "6") (pinfunction "VSS_6") (pintype "power_in"))
    )
    (net (code "53") (name "Net-(C105-Pad1)") (class "Default")
      (node (ref "C105") (pin "1") (pinfunction "1_1") (pintype "passive"))
      (node (ref "C106") (pin "1") (pinfunction "1_1") (pintype "passive"))
      (node (ref "C107") (pin "1") (pinfunction "1_1") (pintype "passive"))
      (node (ref "R109") (pin "1") (pinfunction "1_1") (pintype "passive"))
      (node (ref "R139") (pin "1") (pinfunction "1_1") (pintype "passive"))
      (node (ref "R140") (pin "1") (pinfunction "1_1") (pintype "passive"))
    )
    (net (code "54") (name "Net-(C105-Pad2)") (class "Default")
      (node (ref "C105") (pin "2") (pinfunction "2_2") (pintype "passive"))
      (node (ref "L101") (pin "2") (pinfunction "2_2") (pintype "passive"))
      (node (ref "R105") (pin "1") (pinfunction "1_1") (pintype "passive"))
    )
    (net (code "55") (name "Net-(C106-Pad2)") (class "Default")
      (node (ref "C106") (pin "2") (pinfunction "2_2") (pintype "passive"))
      (node (ref "L102") (pin "2") (pinfunction "2_2") (pintype "passive"))
      (node (ref "R106") (pin "1") (pinfunction "1_1") (pintype "passive"))
    )
    (net (code "56") (name "Net-(C107-Pad2)") (class "Default")
      (node (ref "C107") (pin "2") (pinfunction "2_2") (pintype "passive"))
      (node (ref "L103") (pin "2") (pinfunction "2_2") (pintype "passive"))
      (node (ref "R107") (pin "1") (pinfunction "1_1") (pintype "passive"))
    )
    (net (code "57") (name "Net-(P103-Pad1)") (class "Default")
      (node (ref "P103") (pin "1") (pinfunction "1_1") (pintype "passive"))
      (node (ref "P103") (pin "2") (pinfunction "2_2") (pintype "passive"))
      (node (ref "R105") (pin "4") (pinfunction "4_4") (pintype "passive"))
      (node (ref "R112") (pin "2") (pinfunction "2_2") (pintype "passive"))
    )
    (net (code "58") (name "Net-(P104-Pad1)") (class "Default")
      (node (ref "P104") (pin "1") (pinfunction "1_1") (pintype "passive"))
      (node (ref "P104") (pin "2") (pinfunction "2_2") (pintype "passive"))
      (node (ref "R106") (pin "4") (pinfunction "4_4") (pintype "passive"))
      (node (ref "R115") (pin "2") (pinfunction "2_2") (pintype "passive"))
    )
    (net (code "59") (name "Net-(P105-Pad1)") (class "Default")
      (node (ref "P105") (pin "1") (pinfunction "1_1") (pintype "passive"))
      (node (ref "P105") (pin "2") (pinfunction "2_2") (pintype "passive"))
      (node (ref "R107") (pin "4") (pinfunction "4_4") (pintype "passive"))
      (node (ref "R118") (pin "2") (pinfunction "2_2") (pintype "passive"))
    )
    (net (code "60") (name "Net-(Q101-D)") (class "Default")
      (node (ref "Q101") (pin "3") (pinfunction "D_3") (pintype "passive"))
      (node (ref "Q103") (pin "3") (pinfunction "D_3") (pintype "passive"))
      (node (ref "Q105") (pin "3") (pinfunction "D_3") (pintype "passive"))
      (node (ref "R101") (pin "4") (pinfunction "4_4") (pintype "passive"))
      (node (ref "R102") (pin "2") (pinfunction "2_2") (pintype "passive"))
    )
    (net (code "61") (name "Net-(R102-Pad1)") (class "Default")
      (node (ref "R102") (pin "1") (pinfunction "1_1") (pintype "passive"))
      (node (ref "R103") (pin "2") (pinfunction "2_2") (pintype "passive"))
      (node (ref "R104") (pin "2") (pinfunction "2_2") (pintype "passive"))
    )
    (net (code "62") (name "Net-(R112-Pad1)") (class "Default")
      (node (ref "R112") (pin "1") (pinfunction "1_1") (pintype "passive"))
      (node (ref "R113") (pin "2") (pinfunction "2_2") (pintype "passive"))
      (node (ref "R114") (pin "2") (pinfunction "2_2") (pintype "passive"))
    )
    (net (code "63") (name "Net-(R115-Pad1)") (class "Default")
      (node (ref "R115") (pin "1") (pinfunction "1_1") (pintype "passive"))
      (node (ref "R116") (pin "2") (pinfunction "2_2") (pintype "passive"))
      (node (ref "R117") (pin "2") (pinfunction "2_2") (pintype "passive"))
    )
    (net (code "64") (name "Net-(R118-Pad1)") (class "Default")
      (node (ref "R118") (pin "1") (pinfunction "1_1") (pintype "passive"))
      (node (ref "R119") (pin "2") (pinfunction "2_2") (pintype "passive"))
      (node (ref "R120") (pin "2") (pinfunction "2_2") (pintype "passive"))
    )
    (net (code "65") (name "Net-(R135-TOP)") (class "Default")
      (node (ref "R134") (pin "1") (pinfunction "1_1") (pintype "passive"))
      (node (ref "R135") (pin "1") (pinfunction "TOP_1") (pintype "passive"))
    )
    (net (code "66") (name "Net-(R138-TOP)") (class "Default")
      (node (ref "R137") (pin "1") (pinfunction "1_1") (pintype "passive"))
      (node (ref "R138") (pin "1") (pinfunction "TOP_1") (pintype "passive"))
    )
    (net (code "67") (name "Net-(U101-REFIN{slash}OUT)") (class "Default")
      (node (ref "C120") (pin "2") (pinfunction "2_2") (pintype "passive"))
      (node (ref "U101") (pin "5") (pinfunction "REFIN/OUT_5") (pintype "bidirectional"))
    )
    (net (code "68") (name "Net-(U102-ADJ)") (class "Default")
      (node (ref "R133") (pin "2") (pinfunction "2_2") (pintype "passive"))
      (node (ref "R134") (pin "2") (pinfunction "2_2") (pintype "passive"))
      (node (ref "U102") (pin "3") (pinfunction "ADJ_3") (pintype "power_in"))
    )
    (net (code "69") (name "Net-(U103-ADJ)") (class "Default")
      (node (ref "R136") (pin "2") (pinfunction "2_2") (pintype "passive"))
      (node (ref "R137") (pin "2") (pinfunction "2_2") (pintype "passive"))
      (node (ref "U103") (pin "3") (pinfunction "ADJ_3") (pintype "power_in"))
    )
    (net (code "70") (name "Shield") (class "Default")
      (node (ref "R141") (pin "1") (pinfunction "1_1") (pintype "passive"))
    )
    (net (code "71") (name "unconnected-(P106-Pad13)") (class "Default")
      (node (ref "P106") (pin "13") (pinfunction "13_13") (pintype "passive"))
    )
    (net (code "72") (name "unconnected-(P106-Pad15)") (class "Default")
      (node (ref "P106") (pin "15") (pinfunction "15_15") (pintype "passive"))
    )
  )
)
